# Sheet1.net
KiCad netlist of a schematic drawn in Altium Designer
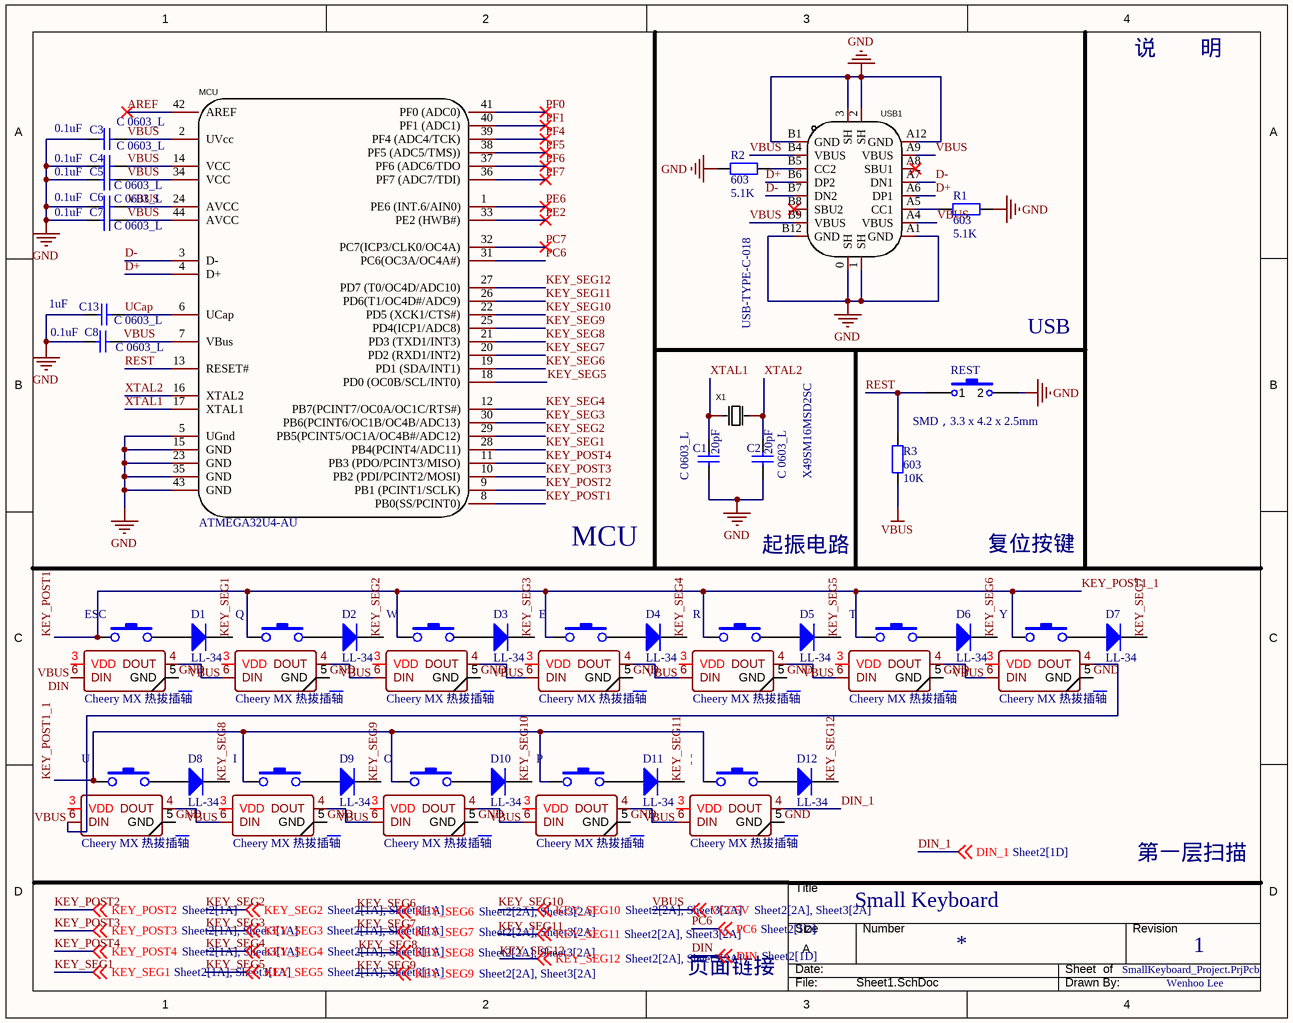
[diagram p0: Sheet1.SchDoc]

(export (version "E")
  (design (tool "Eeschema 10.0.6"))
  (components
    (comp (ref "C1")
      (value "C 0603_L")
      (footprint "C 0603_L")
      (description "贴片电容器（Capacitor）")
      (fields (field (name "ALTIUM_VALUE") "20pF") (field (name "PUBLISHER") "Altium Limited"))
      (libsource (lib "BaseLib") (part "C 0603_L"))
    )
    (comp (ref "C2")
      (value "C 0603_L")
      (footprint "C 0603_L")
      (description "贴片电容器（Capacitor）")
      (fields (field (name "ALTIUM_VALUE") "20pF") (field (name "PUBLISHER") "Altium Limited"))
      (libsource (lib "BaseLib") (part "C 0603_L"))
    )
    (comp (ref "C3")
      (value "C 0603_L")
      (footprint "C 0603_L")
      (description "贴片电容器（Capacitor）")
      (fields (field (name "ALTIUM_VALUE") "0.1uF") (field (name "PUBLISHER") "Altium Limited"))
      (libsource (lib "BaseLib") (part "C 0603_L"))
    )
    (comp (ref "C4")
      (value "C 0603_L")
      (footprint "C 0603_L")
      (description "贴片电容器（Capacitor）")
      (fields (field (name "ALTIUM_VALUE") "0.1uF") (field (name "PUBLISHER") "Altium Limited"))
      (libsource (lib "BaseLib") (part "C 0603_L"))
    )
    (comp (ref "C5")
      (value "C 0603_L")
      (footprint "C 0603_L")
      (description "贴片电容器（Capacitor）")
      (fields (field (name "ALTIUM_VALUE") "0.1uF") (field (name "PUBLISHER") "Altium Limited"))
      (libsource (lib "BaseLib") (part "C 0603_L"))
    )
    (comp (ref "C6")
      (value "C 0603_L")
      (footprint "C 0603_L")
      (description "贴片电容器（Capacitor）")
      (fields (field (name "ALTIUM_VALUE") "0.1uF") (field (name "PUBLISHER") "Altium Limited"))
      (libsource (lib "BaseLib") (part "C 0603_L"))
    )
    (comp (ref "C7")
      (value "C 0603_L")
      (footprint "C 0603_L")
      (description "贴片电容器（Capacitor）")
      (fields (field (name "ALTIUM_VALUE") "0.1uF") (field (name "PUBLISHER") "Altium Limited"))
      (libsource (lib "BaseLib") (part "C 0603_L"))
    )
    (comp (ref "C8")
      (value "C 0603_L")
      (footprint "C 0603_L")
      (description "贴片电容器（Capacitor）")
      (fields (field (name "ALTIUM_VALUE") "0.1uF") (field (name "PUBLISHER") "Altium Limited"))
      (libsource (lib "BaseLib") (part "C 0603_L"))
    )
    (comp (ref "C13")
      (value "C 0603_L")
      (footprint "C 0603_L")
      (description "贴片电容器（Capacitor）")
      (fields (field (name "ALTIUM_VALUE") "1uF") (field (name "PUBLISHER") "Altium Limited"))
      (libsource (lib "BaseLib") (part "C 0603_L"))
    )
    (comp (ref "D1")
      (value "LL-34")
      (footprint "LL-34_L3.7-W1.6-RD")
      (description "开关二极管（Switching diode）")
      (fields (field (name "PUBLISHER") "Altium Limited"))
      (libsource (lib "BaseLib") (part "LL4148"))
    )
    (comp (ref "D2")
      (value "LL-34")
      (footprint "LL-34_L3.7-W1.6-RD")
      (description "开关二极管（Switching diode）")
      (fields (field (name "PUBLISHER") "Altium Limited"))
      (libsource (lib "BaseLib") (part "LL4148"))
    )
    (comp (ref "D3")
      (value "LL-34")
      (footprint "LL-34_L3.7-W1.6-RD")
      (description "开关二极管（Switching diode）")
      (fields (field (name "PUBLISHER") "Altium Limited"))
      (libsource (lib "BaseLib") (part "LL4148"))
    )
    (comp (ref "D4")
      (value "LL-34")
      (footprint "LL-34_L3.7-W1.6-RD")
      (description "开关二极管（Switching diode）")
      (fields (field (name "PUBLISHER") "Altium Limited"))
      (libsource (lib "BaseLib") (part "LL4148"))
    )
    (comp (ref "D5")
      (value "LL-34")
      (footprint "LL-34_L3.7-W1.6-RD")
      (description "开关二极管（Switching diode）")
      (fields (field (name "PUBLISHER") "Altium Limited"))
      (libsource (lib "BaseLib") (part "LL4148"))
    )
    (comp (ref "D6")
      (value "LL-34")
      (footprint "LL-34_L3.7-W1.6-RD")
      (description "开关二极管（Switching diode）")
      (fields (field (name "PUBLISHER") "Altium Limited"))
      (libsource (lib "BaseLib") (part "LL4148"))
    )
    (comp (ref "D7")
      (value "LL-34")
      (footprint "LL-34_L3.7-W1.6-RD")
      (description "开关二极管（Switching diode）")
      (fields (field (name "PUBLISHER") "Altium Limited"))
      (libsource (lib "BaseLib") (part "LL4148"))
    )
    (comp (ref "D8")
      (value "LL-34")
      (footprint "LL-34_L3.7-W1.6-RD")
      (description "开关二极管（Switching diode）")
      (fields (field (name "PUBLISHER") "Altium Limited"))
      (libsource (lib "BaseLib") (part "LL4148"))
    )
    (comp (ref "D9")
      (value "LL-34")
      (footprint "LL-34_L3.7-W1.6-RD")
      (description "开关二极管（Switching diode）")
      (fields (field (name "PUBLISHER") "Altium Limited"))
      (libsource (lib "BaseLib") (part "LL4148"))
    )
    (comp (ref "D10")
      (value "LL-34")
      (footprint "LL-34_L3.7-W1.6-RD")
      (description "开关二极管（Switching diode）")
      (fields (field (name "PUBLISHER") "Altium Limited"))
      (libsource (lib "BaseLib") (part "LL4148"))
    )
    (comp (ref "D11")
      (value "LL-34")
      (footprint "LL-34_L3.7-W1.6-RD")
      (description "开关二极管（Switching diode）")
      (fields (field (name "PUBLISHER") "Altium Limited"))
      (libsource (lib "BaseLib") (part "LL4148"))
    )
    (comp (ref "D12")
      (value "LL-34")
      (footprint "LL-34_L3.7-W1.6-RD")
      (description "开关二极管（Switching diode）")
      (fields (field (name "PUBLISHER") "Altium Limited"))
      (libsource (lib "BaseLib") (part "LL4148"))
    )
    (comp (ref "E")
      (value "Cheery MX 热拔插轴")
      (footprint "MX_SW-HOTPLUG")
      (description "机械键盘轴（Cheery MX）")
      (libsource (lib "BaseLib") (part "Cheery MX 热拔插轴"))
    )
    (comp (ref "ESC")
      (value "Cheery MX 热拔插轴")
      (footprint "MX_SW-HOTPLUG")
      (description "机械键盘轴（Cheery MX）")
      (libsource (lib "BaseLib") (part "Cheery MX 热拔插轴"))
    )
    (comp (ref "I")
      (value "Cheery MX 热拔插轴")
      (footprint "MX_SW-HOTPLUG")
      (description "机械键盘轴（Cheery MX）")
      (libsource (lib "BaseLib") (part "Cheery MX 热拔插轴"))
    )
    (comp (ref "MCU")
      (value "ATMEGA32U4-AU")
      (footprint "QFP-44_L10.0-W10.0-P0.80-LS13.2-BL")
      (description "MCU，ATMEGA32U4-AU")
      (fields (field (name "MANUFACTURER") "MICROCHIP(美国微芯)"))
      (libsource (lib "BaseLib") (part "ATMEGA32U4-AU"))
    )
    (comp (ref "O")
      (value "Cheery MX 热拔插轴")
      (footprint "MX_SW-HOTPLUG")
      (description "机械键盘轴（Cheery MX）")
      (libsource (lib "BaseLib") (part "Cheery MX 热拔插轴"))
    )
    (comp (ref "P")
      (value "Cheery MX 热拔插轴")
      (footprint "MX_SW-HOTPLUG")
      (description "机械键盘轴（Cheery MX）")
      (libsource (lib "BaseLib") (part "Cheery MX 热拔插轴"))
    )
    (comp (ref "Q")
      (value "Cheery MX 热拔插轴")
      (footprint "MX_SW-HOTPLUG")
      (description "机械键盘轴（Cheery MX）")
      (libsource (lib "BaseLib") (part "Cheery MX 热拔插轴"))
    )
    (comp (ref "R")
      (value "Cheery MX 热拔插轴")
      (footprint "MX_SW-HOTPLUG")
      (description "机械键盘轴（Cheery MX）")
      (libsource (lib "BaseLib") (part "Cheery MX 热拔插轴"))
    )
    (comp (ref "R1")
      (value "603")
      (footprint "0603P")
      (description "贴片电阻（Resistor）")
      (fields (field (name "ALTIUM_VALUE") "5.1K") (field (name "PUBLISHER") "Altium Limited"))
      (libsource (lib "BaseLib") (part "R 0603_P"))
    )
    (comp (ref "R2")
      (value "603")
      (footprint "0603P")
      (description "贴片电阻（Resistor）")
      (fields (field (name "ALTIUM_VALUE") "5.1K") (field (name "PUBLISHER") "Altium Limited"))
      (libsource (lib "BaseLib") (part "R 0603_P"))
    )
    (comp (ref "R3")
      (value "603")
      (footprint "R 0603_L")
      (description "贴片电阻（Resistor）")
      (fields (field (name "ALTIUM_VALUE") "10K") (field (name "PUBLISHER") "Altium Limited"))
      (libsource (lib "BaseLib") (part "R 0603_L"))
    )
    (comp (ref "REST")
      (value "SMD，3.3 x 4.2 x 2.5mm")
      (footprint "SMD-3.2*4.2")
      (description "轻触开关（Touch Switch）")
      (fields (field (name "PUBLISHER") "Altium Limited"))
      (libsource (lib "BaseLib") (part "260GF"))
    )
    (comp (ref "T")
      (value "Cheery MX 热拔插轴")
      (footprint "MX_SW-HOTPLUG")
      (description "机械键盘轴（Cheery MX）")
      (libsource (lib "BaseLib") (part "Cheery MX 热拔插轴"))
    )
    (comp (ref "U")
      (value "Cheery MX 热拔插轴")
      (footprint "MX_SW-HOTPLUG")
      (description "机械键盘轴（Cheery MX）")
      (libsource (lib "BaseLib") (part "Cheery MX 热拔插轴"))
    )
    (comp (ref "USB1")
      (value "USB-TYPE-C-018")
      (footprint "USB-C_SMD-TYPE-C-31-M-12")
      (description "通用通信总线接口（USB）,16pin")
      (fields (field (name "MANUFACTURER") "DEALON(德艺隆)"))
      (libsource (lib "BaseLib") (part "USB-TYPE-C-018"))
    )
    (comp (ref "W")
      (value "Cheery MX 热拔插轴")
      (footprint "MX_SW-HOTPLUG")
      (description "机械键盘轴（Cheery MX）")
      (libsource (lib "BaseLib") (part "Cheery MX 热拔插轴"))
    )
    (comp (ref "X1")
      (value "X49SM16MSD2SC")
      (footprint "HC-49S_L11.4-W4.8")
      (description "无源晶振，2PIN")
      (fields (field (name "MANUFACTURER") "YXC(扬兴晶振)"))
      (libsource (lib "BaseLib") (part "X49SM16MSD2SC"))
    )
    (comp (ref "Y")
      (value "Cheery MX 热拔插轴")
      (footprint "MX_SW-HOTPLUG")
      (description "机械键盘轴（Cheery MX）")
      (libsource (lib "BaseLib") (part "Cheery MX 热拔插轴"))
    )
    (comp (ref "¦")
      (value "Cheery MX 热拔插轴")
      (footprint "MX_SW-HOTPLUG")
      (description "机械键盘轴（Cheery MX）")
      (libsource (lib "BaseLib") (part "Cheery MX 热拔插轴"))
    )
  )
  (nets
    (net (code "1") (name "/AREF") (class "Default")
      (node (ref "MCU") (pin "42") (pinfunction "AREF_42") (pintype "passive+no_connect"))
    )
    (net (code "2") (name "/D+") (class "Default")
      (node (ref "MCU") (pin "4") (pinfunction "D+_4") (pintype "passive"))
      (node (ref "USB1") (pin "A6") (pinfunction "DP1_A6") (pintype "passive"))
      (node (ref "USB1") (pin "B6") (pinfunction "DP2_B6") (pintype "passive"))
    )
    (net (code "3") (name "/D-") (class "Default")
      (node (ref "MCU") (pin "3") (pinfunction "D-_3") (pintype "passive"))
      (node (ref "USB1") (pin "A7") (pinfunction "DN1_A7") (pintype "passive"))
      (node (ref "USB1") (pin "B7") (pinfunction "DN2_B7") (pintype "passive"))
    )
    (net (code "4") (name "/KEY_POST1") (class "Default")
      (node (ref "E") (pin "1") (pinfunction "1_1") (pintype "passive"))
      (node (ref "ESC") (pin "1") (pinfunction "1_1") (pintype "passive"))
      (node (ref "I") (pin "1") (pinfunction "1_1") (pintype "passive"))
      (node (ref "MCU") (pin "8") (pinfunction "PB0(SS/PCINT0)_8") (pintype "passive"))
      (node (ref "O") (pin "1") (pinfunction "1_1") (pintype "passive"))
      (node (ref "P") (pin "1") (pinfunction "1_1") (pintype "passive"))
      (node (ref "Q") (pin "1") (pinfunction "1_1") (pintype "passive"))
      (node (ref "R") (pin "1") (pinfunction "1_1") (pintype "passive"))
      (node (ref "T") (pin "1") (pinfunction "1_1") (pintype "passive"))
      (node (ref "U") (pin "1") (pinfunction "1_1") (pintype "passive"))
      (node (ref "W") (pin "1") (pinfunction "1_1") (pintype "passive"))
      (node (ref "Y") (pin "1") (pinfunction "1_1") (pintype "passive"))
      (node (ref "¦") (pin "1") (pinfunction "1_1") (pintype "passive"))
    )
    (net (code "5") (name "/PC7") (class "Default")
      (node (ref "MCU") (pin "32") (pinfunction "PC7(ICP3/CLK0/OC4A)_32") (pintype "passive+no_connect"))
    )
    (net (code "6") (name "/PE2") (class "Default")
      (node (ref "MCU") (pin "33") (pinfunction "PE2_(HWB#)_33") (pintype "passive+no_connect"))
    )
    (net (code "7") (name "/PE6") (class "Default")
      (node (ref "MCU") (pin "1") (pinfunction "PE6_(INT.6/AIN0)_1") (pintype "passive+no_connect"))
    )
    (net (code "8") (name "/PF0") (class "Default")
      (node (ref "MCU") (pin "41") (pinfunction "PF0_(ADC0)_41") (pintype "passive+no_connect"))
    )
    (net (code "9") (name "/PF1") (class "Default")
      (node (ref "MCU") (pin "40") (pinfunction "PF1_(ADC1)_40") (pintype "passive+no_connect"))
    )
    (net (code "10") (name "/PF4") (class "Default")
      (node (ref "MCU") (pin "39") (pinfunction "PF4_(ADC4/TCK)_39") (pintype "passive+no_connect"))
    )
    (net (code "11") (name "/PF5") (class "Default")
      (node (ref "MCU") (pin "38") (pinfunction "PF5_(ADC5/TMS))_38") (pintype "passive+no_connect"))
    )
    (net (code "12") (name "/PF6") (class "Default")
      (node (ref "MCU") (pin "37") (pinfunction "PF6_(ADC6/TDO_37") (pintype "passive+no_connect"))
    )
    (net (code "13") (name "/PF7") (class "Default")
      (node (ref "MCU") (pin "36") (pinfunction "PF7_(ADC7/TDI)_36") (pintype "passive+no_connect"))
    )
    (net (code "14") (name "/REST") (class "Default")
      (node (ref "MCU") (pin "13") (pinfunction "RESET#_13") (pintype "passive"))
      (node (ref "R3") (pin "2") (pinfunction "2_2") (pintype "passive"))
      (node (ref "REST") (pin "1") (pinfunction "1_1") (pintype "passive"))
    )
    (net (code "15") (name "/UCap") (class "Default")
      (node (ref "C13") (pin "2") (pinfunction "2_2") (pintype "passive"))
      (node (ref "MCU") (pin "6") (pinfunction "UCap_6") (pintype "passive"))
    )
    (net (code "16") (name "/XTAL1") (class "Default")
      (node (ref "C1") (pin "2") (pinfunction "2_2") (pintype "passive"))
      (node (ref "MCU") (pin "17") (pinfunction "XTAL1_17") (pintype "passive"))
      (node (ref "X1") (pin "1") (pinfunction "OSC1_1") (pintype "passive"))
    )
    (net (code "17") (name "/XTAL2") (class "Default")
      (node (ref "C2") (pin "2") (pinfunction "2_2") (pintype "passive"))
      (node (ref "MCU") (pin "16") (pinfunction "XTAL2_16") (pintype "passive"))
      (node (ref "X1") (pin "2") (pinfunction "OSC2_2") (pintype "passive"))
    )
    (net (code "18") (name "DIN") (class "Default")
      (node (ref "ESC") (pin "6") (pinfunction "DIN_6") (pintype "passive"))
    )
    (net (code "19") (name "DIN_1") (class "Default")
      (node (ref "¦") (pin "4") (pinfunction "DOUT_4") (pintype "passive"))
    )
    (net (code "20") (name "GND") (class "Default")
      (node (ref "C1") (pin "1") (pinfunction "1_1") (pintype "passive"))
      (node (ref "C13") (pin "1") (pinfunction "1_1") (pintype "passive"))
      (node (ref "C2") (pin "1") (pinfunction "1_1") (pintype "passive"))
      (node (ref "C3") (pin "1") (pinfunction "1_1") (pintype "passive"))
      (node (ref "C4") (pin "1") (pinfunction "1_1") (pintype "passive"))
      (node (ref "C5") (pin "1") (pinfunction "1_1") (pintype "passive"))
      (node (ref "C6") (pin "1") (pinfunction "1_1") (pintype "passive"))
      (node (ref "C7") (pin "1") (pinfunction "1_1") (pintype "passive"))
      (node (ref "C8") (pin "1") (pinfunction "1_1") (pintype "passive"))
      (node (ref "E") (pin "5") (pinfunction "GND_5") (pintype "passive"))
      (node (ref "ESC") (pin "5") (pinfunction "GND_5") (pintype "passive"))
      (node (ref "I") (pin "5") (pinfunction "GND_5") (pintype "passive"))
      (node (ref "MCU") (pin "15") (pinfunction "GND_15") (pintype "passive"))
      (node (ref "MCU") (pin "23") (pinfunction "GND_23") (pintype "passive"))
      (node (ref "MCU") (pin "35") (pinfunction "GND_35") (pintype "passive"))
      (node (ref "MCU") (pin "43") (pinfunction "GND_43") (pintype "passive"))
      (node (ref "MCU") (pin "5") (pinfunction "UGnd_5") (pintype "passive"))
      (node (ref "O") (pin "5") (pinfunction "GND_5") (pintype "passive"))
      (node (ref "P") (pin "5") (pinfunction "GND_5") (pintype "passive"))
      (node (ref "Q") (pin "5") (pinfunction "GND_5") (pintype "passive"))
      (node (ref "R") (pin "5") (pinfunction "GND_5") (pintype "passive"))
      (node (ref "R1") (pin "2") (pinfunction "2_2") (pintype "passive"))
      (node (ref "R2") (pin "1") (pinfunction "1_1") (pintype "passive"))
      (node (ref "REST") (pin "2") (pinfunction "2_2") (pintype "passive"))
      (node (ref "T") (pin "5") (pinfunction "GND_5") (pintype "passive"))
      (node (ref "U") (pin "5") (pinfunction "GND_5") (pintype "passive"))
      (node (ref "USB1") (pin "0") (pinfunction "SH_0") (pintype "passive"))
      (node (ref "USB1") (pin "1") (pinfunction "SH_1") (pintype "passive"))
      (node (ref "USB1") (pin "2") (pinfunction "SH_2") (pintype "passive"))
      (node (ref "USB1") (pin "3") (pinfunction "SH_3") (pintype "passive"))
      (node (ref "USB1") (pin "A1") (pinfunction "GND_A1") (pintype "passive"))
      (node (ref "USB1") (pin "A12") (pinfunction "GND_A12") (pintype "passive"))
      (node (ref "USB1") (pin "B1") (pinfunction "GND_B1") (pintype "passive"))
      (node (ref "USB1") (pin "B12") (pinfunction "GND_B12") (pintype "passive"))
      (node (ref "W") (pin "5") (pinfunction "GND_5") (pintype "passive"))
      (node (ref "Y") (pin "5") (pinfunction "GND_5") (pintype "passive"))
      (node (ref "¦") (pin "5") (pinfunction "GND_5") (pintype "passive"))
    )
    (net (code "21") (name "KEY_POST2") (class "Default")
      (node (ref "MCU") (pin "9") (pinfunction "PB1_(PCINT1/SCLK)_9") (pintype "passive"))
    )
    (net (code "22") (name "KEY_POST3") (class "Default")
      (node (ref "MCU") (pin "10") (pinfunction "PB2_(PDI/PCINT2/MOSI)_10") (pintype "passive"))
    )
    (net (code "23") (name "KEY_POST4") (class "Default")
      (node (ref "MCU") (pin "11") (pinfunction "PB3_(PDO/PCINT3/MISO)_11") (pintype "passive"))
    )
    (net (code "24") (name "KEY_SEG1") (class "Default")
      (node (ref "D1") (pin "2") (pinfunction "K_2") (pintype "passive"))
      (node (ref "MCU") (pin "28") (pinfunction "PB4(PCINT4/ADC11)_28") (pintype "passive"))
    )
    (net (code "25") (name "KEY_SEG2") (class "Default")
      (node (ref "D2") (pin "2") (pinfunction "K_2") (pintype "passive"))
      (node (ref "MCU") (pin "29") (pinfunction "PB5(PCINT5/OC1A/OC4B#/ADC12)_29") (pintype "passive"))
    )
    (net (code "26") (name "KEY_SEG3") (class "Default")
      (node (ref "D3") (pin "2") (pinfunction "K_2") (pintype "passive"))
      (node (ref "MCU") (pin "30") (pinfunction "PB6(PCINT6/OC1B/OC4B/ADC13)_30") (pintype "passive"))
    )
    (net (code "27") (name "KEY_SEG4") (class "Default")
      (node (ref "D4") (pin "2") (pinfunction "K_2") (pintype "passive"))
      (node (ref "MCU") (pin "12") (pinfunction "PB7(PCINT7/OC0A/OC1C/RTS#)_12") (pintype "passive"))
    )
    (net (code "28") (name "KEY_SEG5") (class "Default")
      (node (ref "D5") (pin "2") (pinfunction "K_2") (pintype "passive"))
      (node (ref "MCU") (pin "18") (pinfunction "PD0_(OC0B/SCL/INT0)_18") (pintype "passive"))
    )
    (net (code "29") (name "KEY_SEG6") (class "Default")
      (node (ref "D6") (pin "2") (pinfunction "K_2") (pintype "passive"))
      (node (ref "MCU") (pin "19") (pinfunction "PD1_(SDA/INT1)_19") (pintype "passive"))
    )
    (net (code "30") (name "KEY_SEG7") (class "Default")
      (node (ref "D7") (pin "2") (pinfunction "K_2") (pintype "passive"))
      (node (ref "MCU") (pin "20") (pinfunction "PD2_(RXD1/INT2)_20") (pintype "passive"))
    )
    (net (code "31") (name "KEY_SEG8") (class "Default")
      (node (ref "D8") (pin "2") (pinfunction "K_2") (pintype "passive"))
      (node (ref "MCU") (pin "21") (pinfunction "PD3_(TXD1/INT3)_21") (pintype "passive"))
    )
    (net (code "32") (name "KEY_SEG9") (class "Default")
      (node (ref "D9") (pin "2") (pinfunction "K_2") (pintype "passive"))
      (node (ref "MCU") (pin "25") (pinfunction "PD4(ICP1/ADC8)_25") (pintype "passive"))
    )
    (net (code "33") (name "KEY_SEG10") (class "Default")
      (node (ref "D10") (pin "2") (pinfunction "K_2") (pintype "passive"))
      (node (ref "MCU") (pin "22") (pinfunction "PD5_(XCK1/CTS#)_22") (pintype "passive"))
    )
    (net (code "34") (name "KEY_SEG11") (class "Default")
      (node (ref "D11") (pin "2") (pinfunction "K_2") (pintype "passive"))
      (node (ref "MCU") (pin "26") (pinfunction "PD6(T1/OC4D#/ADC9)_26") (pintype "passive"))
    )
    (net (code "35") (name "KEY_SEG12") (class "Default")
      (node (ref "D12") (pin "2") (pinfunction "K_2") (pintype "passive"))
      (node (ref "MCU") (pin "27") (pinfunction "PD7_(T0/OC4D/ADC10)_27") (pintype "passive"))
    )
    (net (code "36") (name "Net-(D1-A)") (class "Default")
      (node (ref "D1") (pin "1") (pinfunction "A_1") (pintype "passive"))
      (node (ref "ESC") (pin "2") (pinfunction "2_2") (pintype "passive"))
    )
    (net (code "37") (name "Net-(D2-A)") (class "Default")
      (node (ref "D2") (pin "1") (pinfunction "A_1") (pintype "passive"))
      (node (ref "Q") (pin "2") (pinfunction "2_2") (pintype "passive"))
    )
    (net (code "38") (name "Net-(D3-A)") (class "Default")
      (node (ref "D3") (pin "1") (pinfunction "A_1") (pintype "passive"))
      (node (ref "W") (pin "2") (pinfunction "2_2") (pintype "passive"))
    )
    (net (code "39") (name "Net-(D4-A)") (class "Default")
      (node (ref "D4") (pin "1") (pinfunction "A_1") (pintype "passive"))
      (node (ref "E") (pin "2") (pinfunction "2_2") (pintype "passive"))
    )
    (net (code "40") (name "Net-(D5-A)") (class "Default")
      (node (ref "D5") (pin "1") (pinfunction "A_1") (pintype "passive"))
      (node (ref "R") (pin "2") (pinfunction "2_2") (pintype "passive"))
    )
    (net (code "41") (name "Net-(D6-A)") (class "Default")
      (node (ref "D6") (pin "1") (pinfunction "A_1") (pintype "passive"))
      (node (ref "T") (pin "2") (pinfunction "2_2") (pintype "passive"))
    )
    (net (code "42") (name "Net-(D7-A)") (class "Default")
      (node (ref "D7") (pin "1") (pinfunction "A_1") (pintype "passive"))
      (node (ref "Y") (pin "2") (pinfunction "2_2") (pintype "passive"))
    )
    (net (code "43") (name "Net-(D8-A)") (class "Default")
      (node (ref "D8") (pin "1") (pinfunction "A_1") (pintype "passive"))
      (node (ref "U") (pin "2") (pinfunction "2_2") (pintype "passive"))
    )
    (net (code "44") (name "Net-(D9-A)") (class "Default")
      (node (ref "D9") (pin "1") (pinfunction "A_1") (pintype "passive"))
      (node (ref "I") (pin "2") (pinfunction "2_2") (pintype "passive"))
    )
    (net (code "45") (name "Net-(D10-A)") (class "Default")
      (node (ref "D10") (pin "1") (pinfunction "A_1") (pintype "passive"))
      (node (ref "O") (pin "2") (pinfunction "2_2") (pintype "passive"))
    )
    (net (code "46") (name "Net-(D11-A)") (class "Default")
      (node (ref "D11") (pin "1") (pinfunction "A_1") (pintype "passive"))
      (node (ref "P") (pin "2") (pinfunction "2_2") (pintype "passive"))
    )
    (net (code "47") (name "Net-(D12-A)") (class "Default")
      (node (ref "D12") (pin "1") (pinfunction "A_1") (pintype "passive"))
      (node (ref "¦") (pin "2") (pinfunction "2_2") (pintype "passive"))
    )
    (net (code "48") (name "Net-(E-DIN)") (class "Default")
      (node (ref "E") (pin "6") (pinfunction "DIN_6") (pintype "passive"))
      (node (ref "W") (pin "4") (pinfunction "DOUT_4") (pintype "passive"))
    )
    (net (code "49") (name "Net-(E-DOUT)") (class "Default")
      (node (ref "E") (pin "4") (pinfunction "DOUT_4") (pintype "passive"))
      (node (ref "R") (pin "6") (pinfunction "DIN_6") (pintype "passive"))
    )
    (net (code "50") (name "Net-(ESC-DOUT)") (class "Default")
      (node (ref "ESC") (pin "4") (pinfunction "DOUT_4") (pintype "passive"))
      (node (ref "Q") (pin "6") (pinfunction "DIN_6") (pintype "passive"))
    )
    (net (code "51") (name "Net-(I-DIN)") (class "Default")
      (node (ref "I") (pin "6") (pinfunction "DIN_6") (pintype "passive"))
      (node (ref "U") (pin "4") (pinfunction "DOUT_4") (pintype "passive"))
    )
    (net (code "52") (name "Net-(I-DOUT)") (class "Default")
      (node (ref "I") (pin "4") (pinfunction "DOUT_4") (pintype "passive"))
      (node (ref "O") (pin "6") (pinfunction "DIN_6") (pintype "passive"))
    )
    (net (code "53") (name "Net-(O-DOUT)") (class "Default")
      (node (ref "O") (pin "4") (pinfunction "DOUT_4") (pintype "passive"))
      (node (ref "P") (pin "6") (pinfunction "DIN_6") (pintype "passive"))
    )
    (net (code "54") (name "Net-(P-DOUT)") (class "Default")
      (node (ref "P") (pin "4") (pinfunction "DOUT_4") (pintype "passive"))
      (node (ref "¦") (pin "6") (pinfunction "DIN_6") (pintype "passive"))
    )
    (net (code "55") (name "Net-(Q-DOUT)") (class "Default")
      (node (ref "Q") (pin "4") (pinfunction "DOUT_4") (pintype "passive"))
      (node (ref "W") (pin "6") (pinfunction "DIN_6") (pintype "passive"))
    )
    (net (code "56") (name "Net-(R-DOUT)") (class "Default")
      (node (ref "R") (pin "4") (pinfunction "DOUT_4") (pintype "passive"))
      (node (ref "T") (pin "6") (pinfunction "DIN_6") (pintype "passive"))
    )
    (net (code "57") (name "Net-(T-DOUT)") (class "Default")
      (node (ref "T") (pin "4") (pinfunction "DOUT_4") (pintype "passive"))
      (node (ref "Y") (pin "6") (pinfunction "DIN_6") (pintype "passive"))
    )
    (net (code "58") (name "Net-(U-DIN)") (class "Default")
      (node (ref "U") (pin "6") (pinfunction "DIN_6") (pintype "passive"))
      (node (ref "Y") (pin "4") (pinfunction "DOUT_4") (pintype "passive"))
    )
    (net (code "59") (name "Net-(USB1-CC1)") (class "Default")
      (node (ref "R1") (pin "1") (pinfunction "1_1") (pintype "passive"))
      (node (ref "USB1") (pin "A5") (pinfunction "CC1_A5") (pintype "passive"))
    )
    (net (code "60") (name "Net-(USB1-CC2)") (class "Default")
      (node (ref "R2") (pin "2") (pinfunction "2_2") (pintype "passive"))
      (node (ref "USB1") (pin "B5") (pinfunction "CC2_B5") (pintype "passive"))
    )
    (net (code "61") (name "PC6") (class "Default")
      (node (ref "MCU") (pin "31") (pinfunction "PC6(OC3A/OC4A#)_31") (pintype "passive"))
    )
    (net (code "62") (name "VBUS") (class "Default")
      (node (ref "C3") (pin "2") (pinfunction "2_2") (pintype "passive"))
      (node (ref "C4") (pin "2") (pinfunction "2_2") (pintype "passive"))
      (node (ref "C5") (pin "2") (pinfunction "2_2") (pintype "passive"))
      (node (ref "C6") (pin "2") (pinfunction "2_2") (pintype "passive"))
      (node (ref "C7") (pin "2") (pinfunction "2_2") (pintype "passive"))
      (node (ref "C8") (pin "2") (pinfunction "2_2") (pintype "passive"))
      (node (ref "E") (pin "3") (pinfunction "VDD_3") (pintype "passive"))
      (node (ref "ESC") (pin "3") (pinfunction "VDD_3") (pintype "passive"))
      (node (ref "I") (pin "3") (pinfunction "VDD_3") (pintype "passive"))
      (node (ref "MCU") (pin "14") (pinfunction "VCC_14") (pintype "passive"))
      (node (ref "MCU") (pin "2") (pinfunction "UVcc_2") (pintype "passive"))
      (node (ref "MCU") (pin "24") (pinfunction "AVCC_24") (pintype "passive"))
      (node (ref "MCU") (pin "34") (pinfunction "VCC_34") (pintype "passive"))
      (node (ref "MCU") (pin "44") (pinfunction "AVCC_44") (pintype "passive"))
      (node (ref "MCU") (pin "7") (pinfunction "VBus_7") (pintype "passive"))
      (node (ref "O") (pin "3") (pinfunction "VDD_3") (pintype "passive"))
      (node (ref "P") (pin "3") (pinfunction "VDD_3") (pintype "passive"))
      (node (ref "Q") (pin "3") (pinfunction "VDD_3") (pintype "passive"))
      (node (ref "R") (pin "3") (pinfunction "VDD_3") (pintype "passive"))
      (node (ref "R3") (pin "1") (pinfunction "1_1") (pintype "passive"))
      (node (ref "T") (pin "3") (pinfunction "VDD_3") (pintype "passive"))
      (node (ref "U") (pin "3") (pinfunction "VDD_3") (pintype "passive"))
      (node (ref "USB1") (pin "A4") (pinfunction "VBUS_A4") (pintype "passive"))
      (node (ref "USB1") (pin "A9") (pinfunction "VBUS_A9") (pintype "passive"))
      (node (ref "USB1") (pin "B4") (pinfunction "VBUS_B4") (pintype "passive"))
      (node (ref "USB1") (pin "B9") (pinfunction "VBUS_B9") (pintype "passive"))
      (node (ref "W") (pin "3") (pinfunction "VDD_3") (pintype "passive"))
      (node (ref "Y") (pin "3") (pinfunction "VDD_3") (pintype "passive"))
      (node (ref "¦") (pin "3") (pinfunction "VDD_3") (pintype "passive"))
    )
    (net (code "63") (name "unconnected-(USB1-SBU1-PadA8)") (class "Default")
      (node (ref "USB1") (pin "A8") (pinfunction "SBU1_A8") (pintype "passive+no_connect"))
    )
    (net (code "64") (name "unconnected-(USB1-SBU2-PadB8)") (class "Default")
      (node (ref "USB1") (pin "B8") (pinfunction "SBU2_B8") (pintype "passive+no_connect"))
    )
  )
)
